# 11_LMS1_Power.net
KiCad netlist of a schematic drawn in Altium Designer
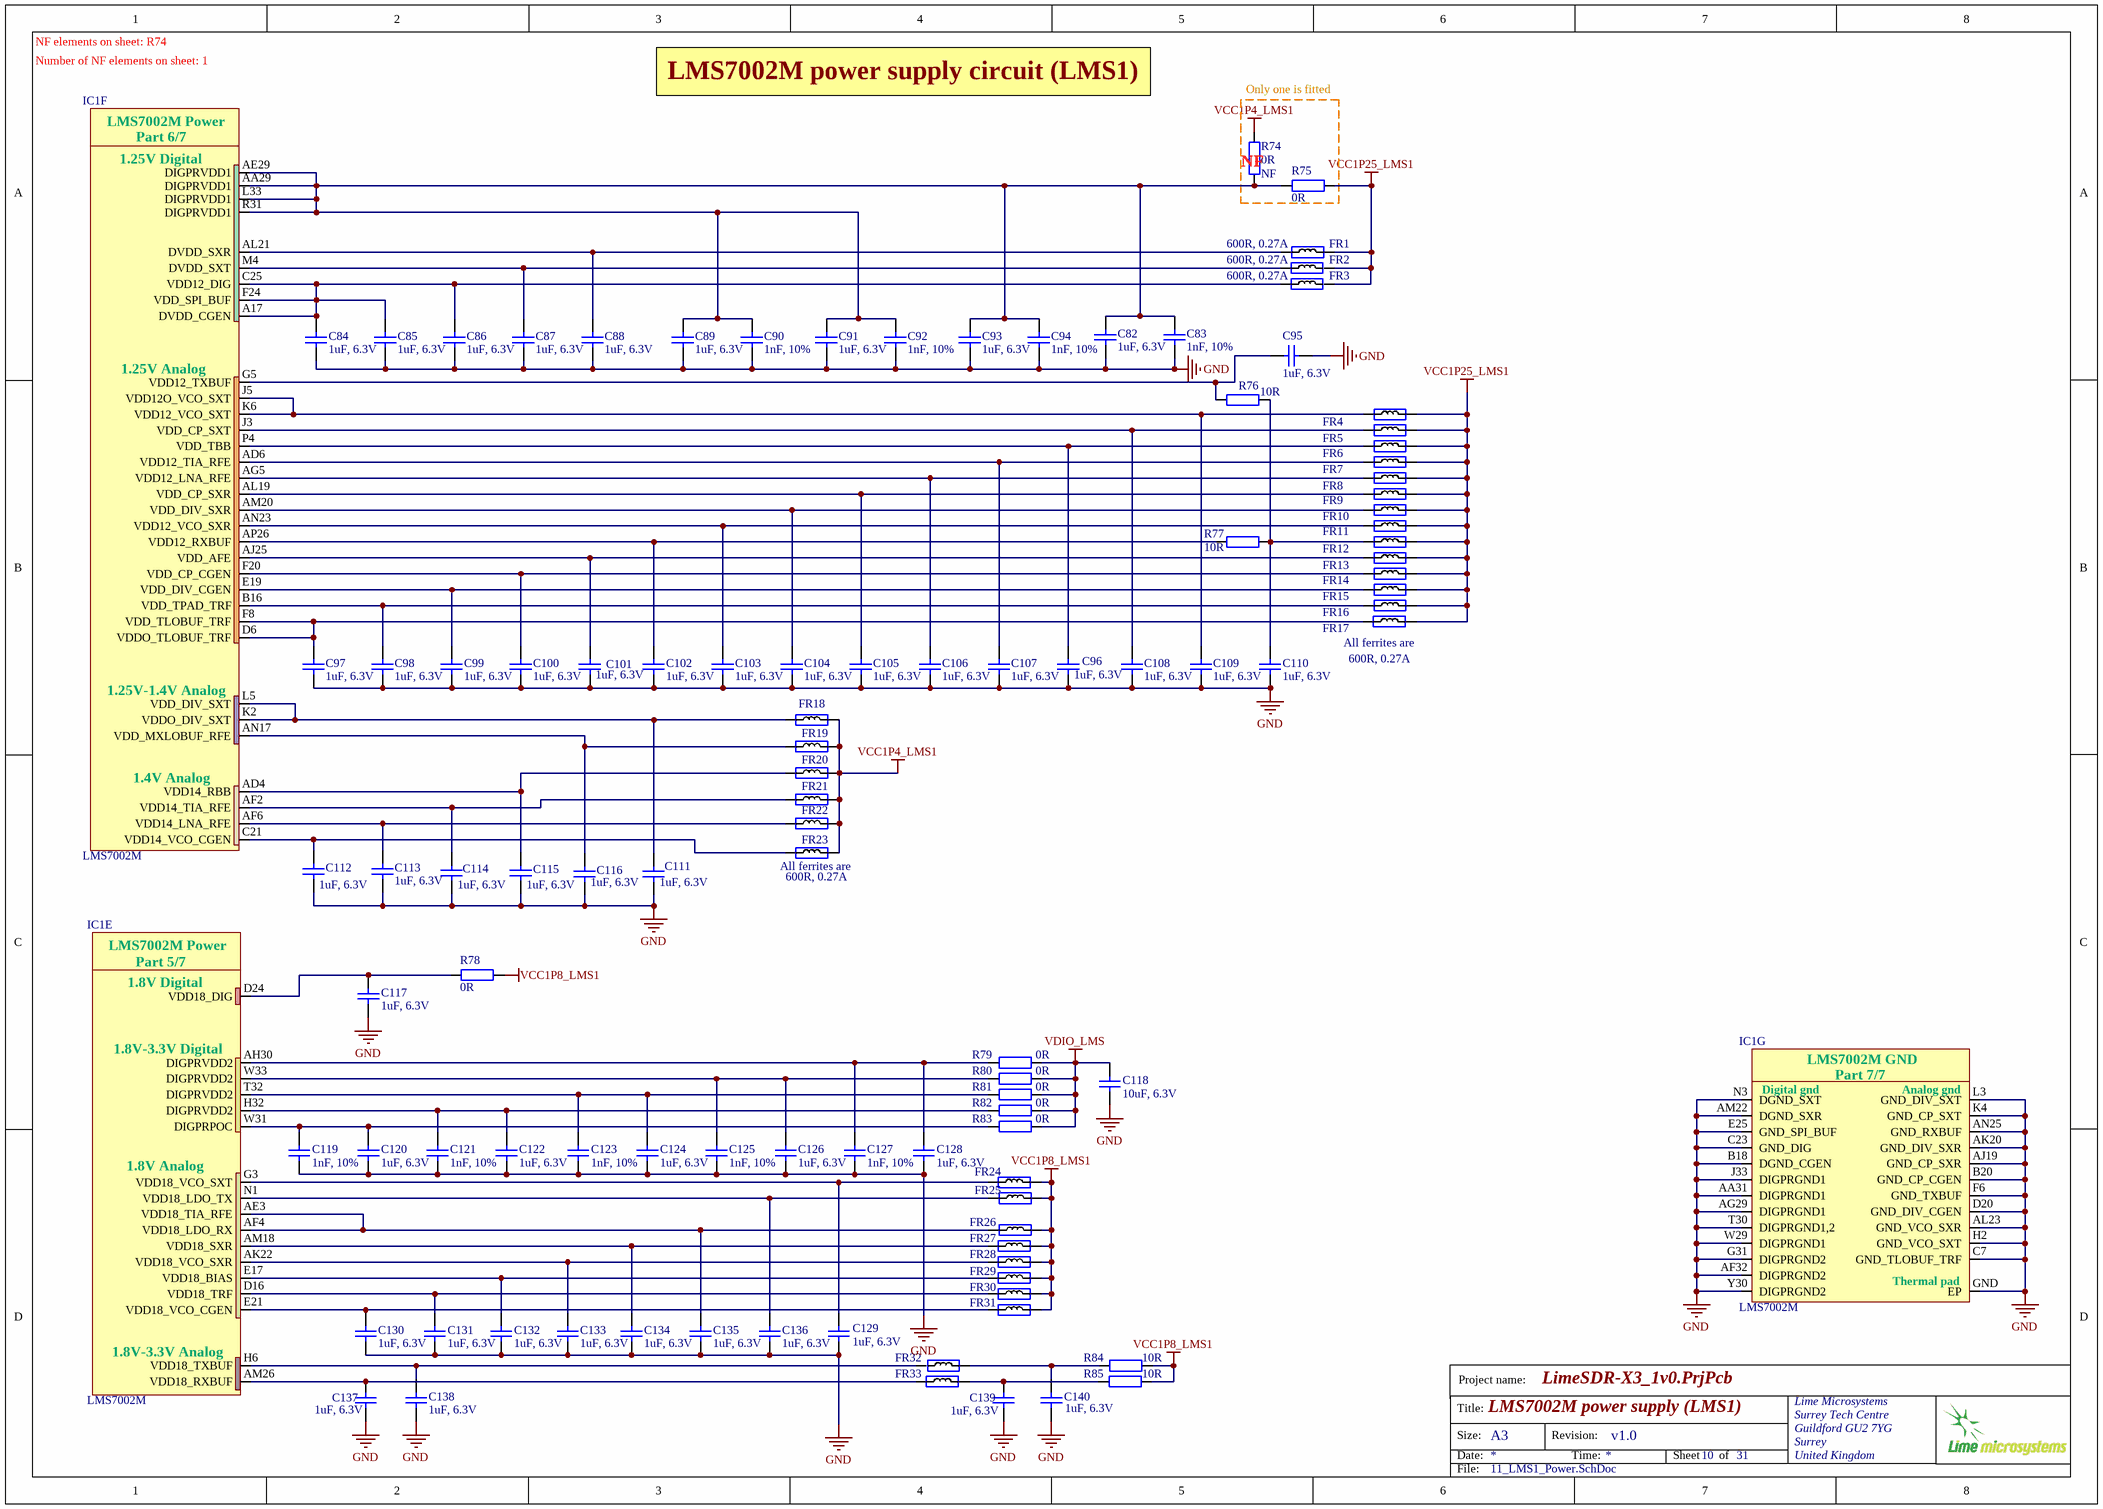
[diagram p0: 11_LMS1_Power.SchDoc]

(export (version "E")
  (design (tool "Eeschema 10.0.6"))
  (components
    (comp (ref "C82")
      (value "1uF, 6.3V")
      (footprint "CAP0201")
      (fields (field (name "TOLERANCE") "±20%") (field (name "MANUFACTURER") "TDK Corporation"))
      (libsource (lib "") (part "Cap_0402_4"))
    )
    (comp (ref "C83")
      (value "1nF, 10%")
      (footprint "CAP0201")
      (fields (field (name "TOLERANCE") "±10%") (field (name "MANUFACTURER") "TDK Corporation"))
      (libsource (lib "") (part "Cap_0402_4"))
    )
    (comp (ref "C84")
      (value "1uF, 6.3V")
      (footprint "CAP0201")
      (fields (field (name "TOLERANCE") "±20%") (field (name "MANUFACTURER") "TDK Corporation"))
      (libsource (lib "") (part "Cap_0402_2"))
    )
    (comp (ref "C85")
      (value "1uF, 6.3V")
      (footprint "CAP0201")
      (fields (field (name "TOLERANCE") "±20%") (field (name "MANUFACTURER") "TDK Corporation"))
      (libsource (lib "") (part "Cap_0402_2"))
    )
    (comp (ref "C86")
      (value "1uF, 6.3V")
      (footprint "CAP0201")
      (fields (field (name "TOLERANCE") "±20%") (field (name "MANUFACTURER") "TDK Corporation"))
      (libsource (lib "") (part "Cap_0402_2"))
    )
    (comp (ref "C87")
      (value "1uF, 6.3V")
      (footprint "CAP0201")
      (fields (field (name "TOLERANCE") "±20%") (field (name "MANUFACTURER") "TDK Corporation"))
      (libsource (lib "") (part "Cap_0402_4"))
    )
    (comp (ref "C88")
      (value "1uF, 6.3V")
      (footprint "CAP0201")
      (fields (field (name "TOLERANCE") "±20%") (field (name "MANUFACTURER") "TDK Corporation"))
      (libsource (lib "") (part "Cap_0402_2"))
    )
    (comp (ref "C89")
      (value "1uF, 6.3V")
      (footprint "CAP0201")
      (fields (field (name "TOLERANCE") "±20%") (field (name "MANUFACTURER") "TDK Corporation"))
      (libsource (lib "") (part "Cap_0402_4"))
    )
    (comp (ref "C90")
      (value "1nF, 10%")
      (footprint "CAP0201")
      (fields (field (name "TOLERANCE") "±10%") (field (name "MANUFACTURER") "TDK Corporation"))
      (libsource (lib "") (part "Cap_0402_4"))
    )
    (comp (ref "C91")
      (value "1uF, 6.3V")
      (footprint "CAP0201")
      (fields (field (name "TOLERANCE") "±20%") (field (name "MANUFACTURER") "TDK Corporation"))
      (libsource (lib "") (part "Cap_0402_4"))
    )
    (comp (ref "C92")
      (value "1nF, 10%")
      (footprint "CAP0201")
      (fields (field (name "TOLERANCE") "±10%") (field (name "MANUFACTURER") "TDK Corporation"))
      (libsource (lib "") (part "Cap_0402_4"))
    )
    (comp (ref "C93")
      (value "1uF, 6.3V")
      (footprint "CAP0201")
      (fields (field (name "TOLERANCE") "±20%") (field (name "MANUFACTURER") "TDK Corporation"))
      (libsource (lib "") (part "Cap_0402_4"))
    )
    (comp (ref "C94")
      (value "1nF, 10%")
      (footprint "CAP0201")
      (fields (field (name "TOLERANCE") "±10%") (field (name "MANUFACTURER") "TDK Corporation"))
      (libsource (lib "") (part "Cap_0402_4"))
    )
    (comp (ref "C95")
      (value "1uF, 6.3V")
      (footprint "CAP0201")
      (fields (field (name "TOLERANCE") "±20%") (field (name "MANUFACTURER") "TDK Corporation"))
      (libsource (lib "") (part "Cap_0402_1"))
    )
    (comp (ref "C96")
      (value "1uF, 6.3V")
      (footprint "CAP0201")
      (fields (field (name "TOLERANCE") "±20%") (field (name "MANUFACTURER") "TDK Corporation"))
      (libsource (lib "") (part "Cap_0402_2"))
    )
    (comp (ref "C97")
      (value "1uF, 6.3V")
      (footprint "CAP0201")
      (fields (field (name "TOLERANCE") "±20%") (field (name "MANUFACTURER") "TDK Corporation"))
      (libsource (lib "") (part "Cap_0402_2"))
    )
    (comp (ref "C98")
      (value "1uF, 6.3V")
      (footprint "CAP0201")
      (fields (field (name "TOLERANCE") "±20%") (field (name "MANUFACTURER") "TDK Corporation"))
      (libsource (lib "") (part "Cap_0402_2"))
    )
    (comp (ref "C99")
      (value "1uF, 6.3V")
      (footprint "CAP0201")
      (fields (field (name "TOLERANCE") "±20%") (field (name "MANUFACTURER") "TDK Corporation"))
      (libsource (lib "") (part "Cap_0402_2"))
    )
    (comp (ref "C100")
      (value "1uF, 6.3V")
      (footprint "CAP0201")
      (fields (field (name "TOLERANCE") "±20%") (field (name "MANUFACTURER") "TDK Corporation"))
      (libsource (lib "") (part "Cap_0402_4"))
    )
    (comp (ref "C101")
      (value "1uF, 6.3V")
      (footprint "CAP0201")
      (fields (field (name "TOLERANCE") "±20%") (field (name "MANUFACTURER") "TDK Corporation"))
      (libsource (lib "") (part "Cap_0402_2"))
    )
    (comp (ref "C102")
      (value "1uF, 6.3V")
      (footprint "CAP0201")
      (fields (field (name "TOLERANCE") "±20%") (field (name "MANUFACTURER") "TDK Corporation"))
      (libsource (lib "") (part "Cap_0402_2"))
    )
    (comp (ref "C103")
      (value "1uF, 6.3V")
      (footprint "CAP0201")
      (fields (field (name "TOLERANCE") "±20%") (field (name "MANUFACTURER") "TDK Corporation"))
      (libsource (lib "") (part "Cap_0402_2"))
    )
    (comp (ref "C104")
      (value "1uF, 6.3V")
      (footprint "CAP0201")
      (fields (field (name "TOLERANCE") "±20%") (field (name "MANUFACTURER") "TDK Corporation"))
      (libsource (lib "") (part "Cap_0402_2"))
    )
    (comp (ref "C105")
      (value "1uF, 6.3V")
      (footprint "CAP0201")
      (fields (field (name "TOLERANCE") "±20%") (field (name "MANUFACTURER") "TDK Corporation"))
      (libsource (lib "") (part "Cap_0402_2"))
    )
    (comp (ref "C106")
      (value "1uF, 6.3V")
      (footprint "CAP0201")
      (fields (field (name "TOLERANCE") "±20%") (field (name "MANUFACTURER") "TDK Corporation"))
      (libsource (lib "") (part "Cap_0402_2"))
    )
    (comp (ref "C107")
      (value "1uF, 6.3V")
      (footprint "CAP0201")
      (fields (field (name "TOLERANCE") "±20%") (field (name "MANUFACTURER") "TDK Corporation"))
      (libsource (lib "") (part "Cap_0402_4"))
    )
    (comp (ref "C108")
      (value "1uF, 6.3V")
      (footprint "CAP0201")
      (fields (field (name "TOLERANCE") "±20%") (field (name "MANUFACTURER") "TDK Corporation"))
      (libsource (lib "") (part "Cap_0402_2"))
    )
    (comp (ref "C109")
      (value "1uF, 6.3V")
      (footprint "CAP0201")
      (fields (field (name "TOLERANCE") "±20%") (field (name "MANUFACTURER") "TDK Corporation"))
      (libsource (lib "") (part "Cap_0402_4"))
    )
    (comp (ref "C110")
      (value "1uF, 6.3V")
      (footprint "CAP0201")
      (fields (field (name "TOLERANCE") "±20%") (field (name "MANUFACTURER") "TDK Corporation"))
      (libsource (lib "") (part "Cap_0402_4"))
    )
    (comp (ref "C111")
      (value "1uF, 6.3V")
      (footprint "CAP0201")
      (fields (field (name "TOLERANCE") "±20%") (field (name "MANUFACTURER") "TDK Corporation"))
      (libsource (lib "") (part "Cap_0402_2"))
    )
    (comp (ref "C112")
      (value "1uF, 6.3V")
      (footprint "CAP0201")
      (fields (field (name "TOLERANCE") "±20%") (field (name "MANUFACTURER") "TDK Corporation"))
      (libsource (lib "") (part "Cap_0402_2"))
    )
    (comp (ref "C113")
      (value "1uF, 6.3V")
      (footprint "CAP0201")
      (fields (field (name "TOLERANCE") "±20%") (field (name "MANUFACTURER") "TDK Corporation"))
      (libsource (lib "") (part "Cap_0402_2"))
    )
    (comp (ref "C114")
      (value "1uF, 6.3V")
      (footprint "CAP0201")
      (fields (field (name "TOLERANCE") "±20%") (field (name "MANUFACTURER") "TDK Corporation"))
      (libsource (lib "") (part "Cap_0402_3"))
    )
    (comp (ref "C115")
      (value "1uF, 6.3V")
      (footprint "CAP0201")
      (fields (field (name "TOLERANCE") "±20%") (field (name "MANUFACTURER") "TDK Corporation"))
      (libsource (lib "") (part "Cap_0402_3"))
    )
    (comp (ref "C116")
      (value "1uF, 6.3V")
      (footprint "CAP0201")
      (fields (field (name "TOLERANCE") "±20%") (field (name "MANUFACTURER") "TDK Corporation"))
      (libsource (lib "") (part "Cap_0402_2"))
    )
    (comp (ref "C117")
      (value "1uF, 6.3V")
      (footprint "CAP0201")
      (fields (field (name "TOLERANCE") "±20%") (field (name "MANUFACTURER") "TDK Corporation"))
      (libsource (lib "LimeMicroAltiumLib_schLib") (part "Cap_0402"))
    )
    (comp (ref "C118")
      (value "10uF, 6.3V")
      (footprint "CAP0603")
      (fields (field (name "TOLERANCE") "±20%") (field (name "MANUFACTURER") "Yageo"))
      (libsource (lib "LimeFPGAboard_schLib") (part "Cap_0603"))
    )
    (comp (ref "C119")
      (value "1nF, 10%")
      (footprint "CAP0201")
      (fields (field (name "TOLERANCE") "±10%") (field (name "MANUFACTURER") "TDK Corporation"))
      (libsource (lib "LimeMicroAltiumLib_schLib") (part "Cap_0402"))
    )
    (comp (ref "C120")
      (value "1uF, 6.3V")
      (footprint "CAP0201")
      (fields (field (name "TOLERANCE") "±20%") (field (name "MANUFACTURER") "TDK Corporation"))
      (libsource (lib "LimeMicroAltiumLib_schLib") (part "Cap_0402"))
    )
    (comp (ref "C121")
      (value "1nF, 10%")
      (footprint "CAP0201")
      (fields (field (name "TOLERANCE") "±10%") (field (name "MANUFACTURER") "TDK Corporation"))
      (libsource (lib "LimeMicroAltiumLib_schLib") (part "Cap_0402"))
    )
    (comp (ref "C122")
      (value "1uF, 6.3V")
      (footprint "CAP0201")
      (fields (field (name "TOLERANCE") "±20%") (field (name "MANUFACTURER") "TDK Corporation"))
      (libsource (lib "LimeMicroAltiumLib_schLib") (part "Cap_0402"))
    )
    (comp (ref "C123")
      (value "1nF, 10%")
      (footprint "CAP0201")
      (fields (field (name "TOLERANCE") "±10%") (field (name "MANUFACTURER") "TDK Corporation"))
      (libsource (lib "LimeMicroAltiumLib_schLib") (part "Cap_0402"))
    )
    (comp (ref "C124")
      (value "1uF, 6.3V")
      (footprint "CAP0201")
      (fields (field (name "TOLERANCE") "±20%") (field (name "MANUFACTURER") "TDK Corporation"))
      (libsource (lib "LimeMicroAltiumLib_schLib") (part "Cap_0402"))
    )
    (comp (ref "C125")
      (value "1nF, 10%")
      (footprint "CAP0201")
      (fields (field (name "TOLERANCE") "±10%") (field (name "MANUFACTURER") "TDK Corporation"))
      (libsource (lib "LimeMicroAltiumLib_schLib") (part "Cap_0402"))
    )
    (comp (ref "C126")
      (value "1uF, 6.3V")
      (footprint "CAP0201")
      (fields (field (name "TOLERANCE") "±20%") (field (name "MANUFACTURER") "TDK Corporation"))
      (libsource (lib "LimeMicroAltiumLib_schLib") (part "Cap_0402"))
    )
    (comp (ref "C127")
      (value "1nF, 10%")
      (footprint "CAP0201")
      (fields (field (name "TOLERANCE") "±10%") (field (name "MANUFACTURER") "TDK Corporation"))
      (libsource (lib "LimeMicroAltiumLib_schLib") (part "Cap_0402"))
    )
    (comp (ref "C128")
      (value "1uF, 6.3V")
      (footprint "CAP0201")
      (fields (field (name "TOLERANCE") "±20%") (field (name "MANUFACTURER") "TDK Corporation"))
      (libsource (lib "LimeMicroAltiumLib_schLib") (part "Cap_0402"))
    )
    (comp (ref "C129")
      (value "1uF, 6.3V")
      (footprint "CAP0201")
      (fields (field (name "TOLERANCE") "±20%") (field (name "MANUFACTURER") "TDK Corporation"))
      (libsource (lib "LimeMicroAltiumLib_schLib") (part "Cap_0402"))
    )
    (comp (ref "C130")
      (value "1uF, 6.3V")
      (footprint "CAP0201")
      (fields (field (name "TOLERANCE") "±20%") (field (name "MANUFACTURER") "TDK Corporation"))
      (libsource (lib "LimeMicroAltiumLib_schLib") (part "Cap_0402"))
    )
    (comp (ref "C131")
      (value "1uF, 6.3V")
      (footprint "CAP0201")
      (fields (field (name "TOLERANCE") "±20%") (field (name "MANUFACTURER") "TDK Corporation"))
      (libsource (lib "LimeMicroAltiumLib_schLib") (part "Cap_0402"))
    )
    (comp (ref "C132")
      (value "1uF, 6.3V")
      (footprint "CAP0201")
      (fields (field (name "TOLERANCE") "±20%") (field (name "MANUFACTURER") "TDK Corporation"))
      (libsource (lib "LimeMicroAltiumLib_schLib") (part "Cap_0402"))
    )
    (comp (ref "C133")
      (value "1uF, 6.3V")
      (footprint "CAP0201")
      (fields (field (name "TOLERANCE") "±20%") (field (name "MANUFACTURER") "TDK Corporation"))
      (libsource (lib "LimeMicroAltiumLib_schLib") (part "Cap_0402"))
    )
    (comp (ref "C134")
      (value "1uF, 6.3V")
      (footprint "CAP0201")
      (fields (field (name "TOLERANCE") "±20%") (field (name "MANUFACTURER") "TDK Corporation"))
      (libsource (lib "LimeMicroAltiumLib_schLib") (part "Cap_0402"))
    )
    (comp (ref "C135")
      (value "1uF, 6.3V")
      (footprint "CAP0201")
      (fields (field (name "TOLERANCE") "±20%") (field (name "MANUFACTURER") "TDK Corporation"))
      (libsource (lib "LimeMicroAltiumLib_schLib") (part "Cap_0402"))
    )
    (comp (ref "C136")
      (value "1uF, 6.3V")
      (footprint "CAP0201")
      (fields (field (name "TOLERANCE") "±20%") (field (name "MANUFACTURER") "TDK Corporation"))
      (libsource (lib "LimeMicroAltiumLib_schLib") (part "Cap_0402"))
    )
    (comp (ref "C137")
      (value "1uF, 6.3V")
      (footprint "CAP0201")
      (fields (field (name "TOLERANCE") "±20%") (field (name "MANUFACTURER") "TDK Corporation"))
      (libsource (lib "LimeMicroAltiumLib_schLib") (part "Cap_0402"))
    )
    (comp (ref "C138")
      (value "1uF, 6.3V")
      (footprint "CAP0201")
      (fields (field (name "TOLERANCE") "±20%") (field (name "MANUFACTURER") "TDK Corporation"))
      (libsource (lib "LimeMicroAltiumLib_schLib") (part "Cap_0402"))
    )
    (comp (ref "C139")
      (value "1uF, 6.3V")
      (footprint "CAP0201")
      (fields (field (name "TOLERANCE") "±20%") (field (name "MANUFACTURER") "TDK Corporation"))
      (libsource (lib "LimeMicroAltiumLib_schLib") (part "Cap_0402"))
    )
    (comp (ref "C140")
      (value "1uF, 6.3V")
      (footprint "CAP0201")
      (fields (field (name "TOLERANCE") "±20%") (field (name "MANUFACTURER") "TDK Corporation"))
      (libsource (lib "LimeMicroAltiumLib_schLib") (part "Cap_0402"))
    )
    (comp (ref "FR1")
      (value "600R, 0.27A")
      (footprint "RES0201")
      (fields (field (name "MANUFACTURER") "Taiyo Yuden"))
      (libsource (lib "LimeMicroAltiumLib_schLib") (part "Ferrite"))
    )
    (comp (ref "FR2")
      (value "600R, 0.27A")
      (footprint "RES0201")
      (fields (field (name "MANUFACTURER") "Taiyo Yuden"))
      (libsource (lib "") (part "Ferrite_2"))
    )
    (comp (ref "FR3")
      (value "600R, 0.27A")
      (footprint "RES0201")
      (fields (field (name "MANUFACTURER") "Taiyo Yuden"))
      (libsource (lib "") (part "Ferrite_2"))
    )
    (comp (ref "FR4")
      (value "600R, 0.27A")
      (footprint "RES0201")
      (fields (field (name "MANUFACTURER") "Taiyo Yuden"))
      (libsource (lib "LimeMicroAltiumLib_schLib") (part "Ferrite"))
    )
    (comp (ref "FR5")
      (value "600R, 0.27A")
      (footprint "RES0201")
      (fields (field (name "MANUFACTURER") "Taiyo Yuden"))
      (libsource (lib "LimeMicroAltiumLib_schLib") (part "Ferrite"))
    )
    (comp (ref "FR6")
      (value "600R, 0.27A")
      (footprint "RES0201")
      (fields (field (name "MANUFACTURER") "Taiyo Yuden"))
      (libsource (lib "LimeMicroAltiumLib_schLib") (part "Ferrite"))
    )
    (comp (ref "FR7")
      (value "600R, 0.27A")
      (footprint "RES0201")
      (fields (field (name "MANUFACTURER") "Taiyo Yuden"))
      (libsource (lib "LimeMicroAltiumLib_schLib") (part "Ferrite"))
    )
    (comp (ref "FR8")
      (value "600R, 0.27A")
      (footprint "RES0201")
      (fields (field (name "MANUFACTURER") "Taiyo Yuden"))
      (libsource (lib "LimeMicroAltiumLib_schLib") (part "Ferrite"))
    )
    (comp (ref "FR9")
      (value "600R, 0.27A")
      (footprint "RES0201")
      (fields (field (name "MANUFACTURER") "Taiyo Yuden"))
      (libsource (lib "LimeMicroAltiumLib_schLib") (part "Ferrite"))
    )
    (comp (ref "FR10")
      (value "600R, 0.27A")
      (footprint "RES0201")
      (fields (field (name "MANUFACTURER") "Taiyo Yuden"))
      (libsource (lib "LimeMicroAltiumLib_schLib") (part "Ferrite"))
    )
    (comp (ref "FR11")
      (value "600R, 0.27A")
      (footprint "RES0201")
      (fields (field (name "MANUFACTURER") "Taiyo Yuden"))
      (libsource (lib "LimeMicroAltiumLib_schLib") (part "Ferrite"))
    )
    (comp (ref "FR12")
      (value "600R, 0.27A")
      (footprint "RES0201")
      (fields (field (name "MANUFACTURER") "Taiyo Yuden"))
      (libsource (lib "LimeMicroAltiumLib_schLib") (part "Ferrite"))
    )
    (comp (ref "FR13")
      (value "600R, 0.27A")
      (footprint "RES0201")
      (fields (field (name "MANUFACTURER") "Taiyo Yuden"))
      (libsource (lib "LimeMicroAltiumLib_schLib") (part "Ferrite"))
    )
    (comp (ref "FR14")
      (value "600R, 0.27A")
      (footprint "RES0201")
      (fields (field (name "MANUFACTURER") "Taiyo Yuden"))
      (libsource (lib "LimeMicroAltiumLib_schLib") (part "Ferrite"))
    )
    (comp (ref "FR15")
      (value "600R, 0.27A")
      (footprint "RES0201")
      (fields (field (name "MANUFACTURER") "Taiyo Yuden"))
      (libsource (lib "LimeMicroAltiumLib_schLib") (part "Ferrite"))
    )
    (comp (ref "FR16")
      (value "600R, 0.27A")
      (footprint "RES0201")
      (fields (field (name "MANUFACTURER") "Taiyo Yuden"))
      (libsource (lib "LimeMicroAltiumLib_schLib") (part "Ferrite"))
    )
    (comp (ref "FR17")
      (value "600R, 0.27A")
      (footprint "RES0201")
      (fields (field (name "MANUFACTURER") "Taiyo Yuden"))
      (libsource (lib "") (part "Ferrite_2"))
    )
    (comp (ref "FR18")
      (value "600R, 0.27A")
      (footprint "RES0201")
      (fields (field (name "MANUFACTURER") "Taiyo Yuden"))
      (libsource (lib "") (part "Ferrite_2"))
    )
    (comp (ref "FR19")
      (value "600R, 0.27A")
      (footprint "RES0201")
      (fields (field (name "MANUFACTURER") "Taiyo Yuden"))
      (libsource (lib "") (part "Ferrite_2"))
    )
    (comp (ref "FR20")
      (value "600R, 0.27A")
      (footprint "RES0201")
      (fields (field (name "MANUFACTURER") "Taiyo Yuden"))
      (libsource (lib "") (part "Ferrite_2"))
    )
    (comp (ref "FR21")
      (value "600R, 0.27A")
      (footprint "RES0201")
      (fields (field (name "MANUFACTURER") "Taiyo Yuden"))
      (libsource (lib "") (part "Ferrite_2"))
    )
    (comp (ref "FR22")
      (value "600R, 0.27A")
      (footprint "RES0201")
      (fields (field (name "MANUFACTURER") "Taiyo Yuden"))
      (libsource (lib "") (part "Ferrite_2"))
    )
    (comp (ref "FR23")
      (value "600R, 0.27A")
      (footprint "RES0201")
      (fields (field (name "MANUFACTURER") "Taiyo Yuden"))
      (libsource (lib "") (part "Ferrite_2"))
    )
    (comp (ref "FR24")
      (value "600R, 0.27A")
      (footprint "RES0201")
      (fields (field (name "MANUFACTURER") "Taiyo Yuden"))
      (libsource (lib "") (part "Ferrite_2"))
    )
    (comp (ref "FR25")
      (value "600R, 0.27A")
      (footprint "RES0201")
      (fields (field (name "MANUFACTURER") "Taiyo Yuden"))
      (libsource (lib "") (part "Ferrite_1"))
    )
    (comp (ref "FR26")
      (value "600R, 0.27A")
      (footprint "RES0201")
      (fields (field (name "MANUFACTURER") "Taiyo Yuden"))
      (libsource (lib "") (part "Ferrite_1"))
    )
    (comp (ref "FR27")
      (value "600R, 0.27A")
      (footprint "RES0201")
      (fields (field (name "MANUFACTURER") "Taiyo Yuden"))
      (libsource (lib "") (part "Ferrite_2"))
    )
    (comp (ref "FR28")
      (value "600R, 0.27A")
      (footprint "RES0201")
      (fields (field (name "MANUFACTURER") "Taiyo Yuden"))
      (libsource (lib "") (part "Ferrite_2"))
    )
    (comp (ref "FR29")
      (value "600R, 0.27A")
      (footprint "RES0201")
      (fields (field (name "MANUFACTURER") "Taiyo Yuden"))
      (libsource (lib "") (part "Ferrite_2"))
    )
    (comp (ref "FR30")
      (value "600R, 0.27A")
      (footprint "RES0201")
      (fields (field (name "MANUFACTURER") "Taiyo Yuden"))
      (libsource (lib "") (part "Ferrite_2"))
    )
    (comp (ref "FR31")
      (value "600R, 0.27A")
      (footprint "RES0201")
      (fields (field (name "MANUFACTURER") "Taiyo Yuden"))
      (libsource (lib "") (part "Ferrite_2"))
    )
    (comp (ref "FR32")
      (value "600R, 0.27A")
      (footprint "RES0201")
      (fields (field (name "MANUFACTURER") "Taiyo Yuden"))
      (libsource (lib "") (part "Ferrite_1"))
    )
    (comp (ref "FR33")
      (value "600R, 0.27A")
      (footprint "RES0201")
      (fields (field (name "MANUFACTURER") "Taiyo Yuden"))
      (libsource (lib "") (part "Ferrite_2"))
    )
    (comp (ref "IC1")
      (value "LMS7002M")
      (footprint "LMS7002M_v5")
      (description "Schematic symbol revision 4. Default footprint - 0.31mm pad")
      (fields (field (name "MANUFACTURER") "Lime Microsystems"))
      (libsource (lib "LimeMicroAltiumLib_schLib_r04") (part "LMS7002Mr4"))
    )
    (comp (ref "R74")
      (value "0R")
      (footprint "RES0402")
      (fields
        (field (name "ASSEMBLY INFO") "NF")
        (field (name "MANUFACTURER") "Yageo")
        (field (name "TOLERANCE") "Jumper")
      )
      (libsource (lib "LimeMicroAltiumLib_schLib") (part "Res_0402"))
    )
    (comp (ref "R75")
      (value "0R")
      (footprint "RES0402")
      (fields (field (name "MANUFACTURER") "Yageo") (field (name "TOLERANCE") "Jumper"))
      (libsource (lib "") (part "Res_0402_1"))
    )
    (comp (ref "R76")
      (value "10R")
      (footprint "RES0201")
      (fields
        (field (name "MANUFACTURER") "Panasonic Electronic Components")
        (field (name "TOLERANCE") "±1%")
      )
      (libsource (lib "LimeMicroAltiumLib_schLib") (part "Res_0402"))
    )
    (comp (ref "R77")
      (value "10R")
      (footprint "RES0201")
      (fields
        (field (name "MANUFACTURER") "Panasonic Electronic Components")
        (field (name "TOLERANCE") "±1%")
      )
      (libsource (lib "LimeMicroAltiumLib_schLib") (part "Res_0402"))
    )
    (comp (ref "R78")
      (value "0R")
      (footprint "RES0201")
      (fields (field (name "MANUFACTURER") "Rohm Semiconductor") (field (name "TOLERANCE") "Jumper"))
      (libsource (lib "LimeMicroAltiumLib_schLib") (part "Res_0402"))
    )
    (comp (ref "R79")
      (value "0R")
      (footprint "RES0402")
      (fields (field (name "MANUFACTURER") "Yageo") (field (name "TOLERANCE") "Jumper"))
      (libsource (lib "LimeMicroAltiumLib_schLib") (part "Res_0402"))
    )
    (comp (ref "R80")
      (value "0R")
      (footprint "RES0402")
      (fields (field (name "MANUFACTURER") "Yageo") (field (name "TOLERANCE") "Jumper"))
      (libsource (lib "LimeMicroAltiumLib_schLib") (part "Res_0402"))
    )
    (comp (ref "R81")
      (value "0R")
      (footprint "RES0402")
      (fields (field (name "MANUFACTURER") "Yageo") (field (name "TOLERANCE") "Jumper"))
      (libsource (lib "LimeMicroAltiumLib_schLib") (part "Res_0402"))
    )
    (comp (ref "R82")
      (value "0R")
      (footprint "RES0402")
      (fields (field (name "MANUFACTURER") "Yageo") (field (name "TOLERANCE") "Jumper"))
      (libsource (lib "LimeMicroAltiumLib_schLib") (part "Res_0402"))
    )
    (comp (ref "R83")
      (value "0R")
      (footprint "RES0402")
      (fields (field (name "MANUFACTURER") "Yageo") (field (name "TOLERANCE") "Jumper"))
      (libsource (lib "LimeMicroAltiumLib_schLib") (part "Res_0402"))
    )
    (comp (ref "R84")
      (value "10R")
      (footprint "RES0201")
      (fields
        (field (name "MANUFACTURER") "Panasonic Electronic Components")
        (field (name "TOLERANCE") "±1%")
      )
      (libsource (lib "LimeMicroAltiumLib_schLib") (part "Res_0402"))
    )
    (comp (ref "R85")
      (value "10R")
      (footprint "RES0201")
      (fields
        (field (name "MANUFACTURER") "Panasonic Electronic Components")
        (field (name "TOLERANCE") "±1%")
      )
      (libsource (lib "LimeMicroAltiumLib_schLib") (part "Res_0402"))
    )
  )
  (nets
    (net (code "1") (name "GND") (class "Default")
      (node (ref "C100") (pin "1") (pinfunction "1_1") (pintype "passive"))
      (node (ref "C101") (pin "2") (pinfunction "2_2") (pintype "passive"))
      (node (ref "C102") (pin "2") (pinfunction "2_2") (pintype "passive"))
      (node (ref "C103") (pin "2") (pinfunction "2_2") (pintype "passive"))
      (node (ref "C104") (pin "2") (pinfunction "2_2") (pintype "passive"))
      (node (ref "C105") (pin "2") (pinfunction "2_2") (pintype "passive"))
      (node (ref "C106") (pin "2") (pinfunction "2_2") (pintype "passive"))
      (node (ref "C107") (pin "1") (pinfunction "1_1") (pintype "passive"))
      (node (ref "C108") (pin "2") (pinfunction "2_2") (pintype "passive"))
      (node (ref "C109") (pin "1") (pinfunction "1_1") (pintype "passive"))
      (node (ref "C110") (pin "1") (pinfunction "1_1") (pintype "passive"))
      (node (ref "C111") (pin "2") (pinfunction "2_2") (pintype "passive"))
      (node (ref "C112") (pin "2") (pinfunction "2_2") (pintype "passive"))
      (node (ref "C113") (pin "2") (pinfunction "2_2") (pintype "passive"))
      (node (ref "C114") (pin "2") (pinfunction "2_2") (pintype "passive"))
      (node (ref "C115") (pin "2") (pinfunction "2_2") (pintype "passive"))
      (node (ref "C116") (pin "2") (pinfunction "2_2") (pintype "passive"))
      (node (ref "C117") (pin "2") (pinfunction "2_2") (pintype "passive"))
      (node (ref "C118") (pin "1") (pinfunction "1_1") (pintype "passive"))
      (node (ref "C119") (pin "2") (pinfunction "2_2") (pintype "passive"))
      (node (ref "C120") (pin "2") (pinfunction "2_2") (pintype "passive"))
      (node (ref "C121") (pin "2") (pinfunction "2_2") (pintype "passive"))
      (node (ref "C122") (pin "2") (pinfunction "2_2") (pintype "passive"))
      (node (ref "C123") (pin "2") (pinfunction "2_2") (pintype "passive"))
      (node (ref "C124") (pin "2") (pinfunction "2_2") (pintype "passive"))
      (node (ref "C125") (pin "2") (pinfunction "2_2") (pintype "passive"))
      (node (ref "C126") (pin "2") (pinfunction "2_2") (pintype "passive"))
      (node (ref "C127") (pin "2") (pinfunction "2_2") (pintype "passive"))
      (node (ref "C128") (pin "2") (pinfunction "2_2") (pintype "passive"))
      (node (ref "C129") (pin "2") (pinfunction "2_2") (pintype "passive"))
      (node (ref "C130") (pin "2") (pinfunction "2_2") (pintype "passive"))
      (node (ref "C131") (pin "2") (pinfunction "2_2") (pintype "passive"))
      (node (ref "C132") (pin "2") (pinfunction "2_2") (pintype "passive"))
      (node (ref "C133") (pin "2") (pinfunction "2_2") (pintype "passive"))
      (node (ref "C134") (pin "2") (pinfunction "2_2") (pintype "passive"))
      (node (ref "C135") (pin "2") (pinfunction "2_2") (pintype "passive"))
      (node (ref "C136") (pin "2") (pinfunction "2_2") (pintype "passive"))
      (node (ref "C137") (pin "2") (pinfunction "2_2") (pintype "passive"))
      (node (ref "C138") (pin "2") (pinfunction "2_2") (pintype "passive"))
      (node (ref "C139") (pin "2") (pinfunction "2_2") (pintype "passive"))
      (node (ref "C140") (pin "2") (pinfunction "2_2") (pintype "passive"))
      (node (ref "C82") (pin "2") (pinfunction "2_2") (pintype "passive"))
      (node (ref "C83") (pin "2") (pinfunction "2_2") (pintype "passive"))
      (node (ref "C84") (pin "2") (pinfunction "2_2") (pintype "passive"))
      (node (ref "C85") (pin "2") (pinfunction "2_2") (pintype "passive"))
      (node (ref "C86") (pin "2") (pinfunction "2_2") (pintype "passive"))
      (node (ref "C87") (pin "1") (pinfunction "1_1") (pintype "passive"))
      (node (ref "C88") (pin "2") (pinfunction "2_2") (pintype "passive"))
      (node (ref "C89") (pin "2") (pinfunction "2_2") (pintype "passive"))
      (node (ref "C90") (pin "2") (pinfunction "2_2") (pintype "passive"))
      (node (ref "C91") (pin "2") (pinfunction "2_2") (pintype "passive"))
      (node (ref "C92") (pin "2") (pinfunction "2_2") (pintype "passive"))
      (node (ref "C93") (pin "2") (pinfunction "2_2") (pintype "passive"))
      (node (ref "C94") (pin "2") (pinfunction "2_2") (pintype "passive"))
      (node (ref "C95") (pin "2") (pinfunction "2_2") (pintype "passive"))
      (node (ref "C96") (pin "2") (pinfunction "2_2") (pintype "passive"))
      (node (ref "C97") (pin "2") (pinfunction "2_2") (pintype "passive"))
      (node (ref "C98") (pin "2") (pinfunction "2_2") (pintype "passive"))
      (node (ref "C99") (pin "2") (pinfunction "2_2") (pintype "passive"))
      (node (ref "IC1") (pin "AA31") (pinfunction "DIGPRGND1_AA31") (pintype "passive"))
      (node (ref "IC1") (pin "AF32") (pinfunction "DIGPRGND2_AF32") (pintype "passive"))
      (node (ref "IC1") (pin "AG29") (pinfunction "DIGPRGND1_AG29") (pintype "passive"))
      (node (ref "IC1") (pin "AJ19") (pinfunction "GND_CP_SXR_AJ19") (pintype "passive"))
      (node (ref "IC1") (pin "AK20") (pinfunction "GND_DIV_SXR_AK20") (pintype "passive"))
      (node (ref "IC1") (pin "AL23") (pinfunction "GND_VCO_SXR_AL23") (pintype "passive"))
      (node (ref "IC1") (pin "AM22") (pinfunction "DGND_SXR_AM22") (pintype "passive"))
      (node (ref "IC1") (pin "AN25") (pinfunction "GND_RXBUF_AN25") (pintype "passive"))
      (node (ref "IC1") (pin "B18") (pinfunction "DGND_CGEN_B18") (pintype "passive"))
      (node (ref "IC1") (pin "B20") (pinfunction "GND_CP_CGEN_B20") (pintype "passive"))
      (node (ref "IC1") (pin "C23") (pinfunction "GND_DIG_C23") (pintype "passive"))
      (node (ref "IC1") (pin "C7") (pinfunction "GND_TLOBUF_TRF_C7") (pintype "passive"))
      (node (ref "IC1") (pin "D20") (pinfunction "GND_DIV_CGEN_D20") (pintype "passive"))
      (node (ref "IC1") (pin "E25") (pinfunction "GND_SPI_BUF_E25") (pintype "passive"))
      (node (ref "IC1") (pin "F6") (pinfunction "GND_TXBUF_F6") (pintype "passive"))
      (node (ref "IC1") (pin "G31") (pinfunction "DIGPRGND2_G31") (pintype "passive"))
      (node (ref "IC1") (pin "GND") (pinfunction "EP_GND") (pintype "passive"))
      (node (ref "IC1") (pin "H2") (pinfunction "GND_VCO_SXT_H2") (pintype "passive"))
      (node (ref "IC1") (pin "J33") (pinfunction "DIGPRGND1_J33") (pintype "passive"))
      (node (ref "IC1") (pin "K4") (pinfunction "GND_CP_SXT_K4") (pintype "passive"))
      (node (ref "IC1") (pin "L3") (pinfunction "GND_DIV_SXT_L3") (pintype "passive"))
      (node (ref "IC1") (pin "N3") (pinfunction "DGND_SXT_N3") (pintype "passive"))
      (node (ref "IC1") (pin "T30") (pinfunction "DIGPRGND1,2_T30") (pintype "passive"))
      (node (ref "IC1") (pin "W29") (pinfunction "DIGPRGND1_W29") (pintype "passive"))
      (node (ref "IC1") (pin "Y30") (pinfunction "DIGPRGND2_Y30") (pintype "passive"))
    )
    (net (code "2") (name "Net-(C82-Pad1)") (class "Default")
      (node (ref "C82") (pin "1") (pinfunction "1_1") (pintype "passive"))
      (node (ref "C83") (pin "1") (pinfunction "1_1") (pintype "passive"))
      (node (ref "C89") (pin "1") (pinfunction "1_1") (pintype "passive"))
      (node (ref "C90") (pin "1") (pinfunction "1_1") (pintype "passive"))
      (node (ref "C91") (pin "1") (pinfunction "1_1") (pintype "passive"))
      (node (ref "C92") (pin "1") (pinfunction "1_1") (pintype "passive"))
      (node (ref "C93") (pin "1") (pinfunction "1_1") (pintype "passive"))
      (node (ref "C94") (pin "1") (pinfunction "1_1") (pintype "passive"))
      (node (ref "IC1") (pin "AA29") (pinfunction "DIGPRVDD1_AA29") (pintype "power_in"))
      (node (ref "IC1") (pin "AE29") (pinfunction "DIGPRVDD1_AE29") (pintype "power_in"))
      (node (ref "IC1") (pin "L33") (pinfunction "DIGPRVDD1_L33") (pintype "power_in"))
      (node (ref "IC1") (pin "R31") (pinfunction "DIGPRVDD1_R31") (pintype "power_in"))
      (node (ref "R74") (pin "2") (pinfunction "2_2") (pintype "passive"))
      (node (ref "R75") (pin "2") (pinfunction "2_2") (pintype "passive"))
    )
    (net (code "3") (name "Net-(C110-Pad2)") (class "Default")
      (node (ref "C110") (pin "2") (pinfunction "2_2") (pintype "passive"))
      (node (ref "FR12") (pin "1") (pinfunction "1_1") (pintype "passive"))
      (node (ref "R76") (pin "2") (pinfunction "2_2") (pintype "passive"))
      (node (ref "R77") (pin "2") (pinfunction "2_2") (pintype "passive"))
    )
    (net (code "4") (name "Net-(C121-Pad1)") (class "Default")
      (node (ref "C121") (pin "1") (pinfunction "1_1") (pintype "passive"))
      (node (ref "C122") (pin "1") (pinfunction "1_1") (pintype "passive"))
      (node (ref "IC1") (pin "H32") (pinfunction "DIGPRVDD2_H32") (pintype "power_in"))
      (node (ref "R82") (pin "2") (pinfunction "2_2") (pintype "passive"))
    )
    (net (code "5") (name "Net-(C123-Pad1)") (class "Default")
      (node (ref "C123") (pin "1") (pinfunction "1_1") (pintype "passive"))
      (node (ref "C124") (pin "1") (pinfunction "1_1") (pintype "passive"))
      (node (ref "IC1") (pin "T32") (pinfunction "DIGPRVDD2_T32") (pintype "power_in"))
      (node (ref "R81") (pin "2") (pinfunction "2_2") (pintype "passive"))
    )
    (net (code "6") (name "Net-(C125-Pad1)") (class "Default")
      (node (ref "C125") (pin "1") (pinfunction "1_1") (pintype "passive"))
      (node (ref "C126") (pin "1") (pinfunction "1_1") (pintype "passive"))
      (node (ref "IC1") (pin "W33") (pinfunction "DIGPRVDD2_W33") (pintype "power_in"))
      (node (ref "R80") (pin "2") (pinfunction "2_2") (pintype "passive"))
    )
    (net (code "7") (name "Net-(C127-Pad1)") (class "Default")
      (node (ref "C127") (pin "1") (pinfunction "1_1") (pintype "passive"))
      (node (ref "C128") (pin "1") (pinfunction "1_1") (pintype "passive"))
      (node (ref "IC1") (pin "AH30") (pinfunction "DIGPRVDD2_AH30") (pintype "power_in"))
      (node (ref "R79") (pin "2") (pinfunction "2_2") (pintype "passive"))
    )
    (net (code "8") (name "Net-(C139-Pad1)") (class "Default")
      (node (ref "C139") (pin "1") (pinfunction "1_1") (pintype "passive"))
      (node (ref "FR33") (pin "2") (pinfunction "2_2") (pintype "passive"))
      (node (ref "R85") (pin "2") (pinfunction "2_2") (pintype "passive"))
    )
    (net (code "9") (name "Net-(C140-Pad1)") (class "Default")
      (node (ref "C140") (pin "1") (pinfunction "1_1") (pintype "passive"))
      (node (ref "FR32") (pin "1") (pinfunction "1_1") (pintype "passive"))
      (node (ref "R84") (pin "1") (pinfunction "1_1") (pintype "passive"))
    )
    (net (code "10") (name "Net-(IC1E-DIGPRPOC)") (class "Default")
      (node (ref "C119") (pin "1") (pinfunction "1_1") (pintype "passive"))
      (node (ref "C120") (pin "1") (pinfunction "1_1") (pintype "passive"))
      (node (ref "IC1") (pin "W31") (pinfunction "DIGPRPOC_W31") (pintype "power_in"))
      (node (ref "R83") (pin "2") (pinfunction "2_2") (pintype "passive"))
    )
    (net (code "11") (name "Net-(IC1E-VDD18_BIAS)") (class "Default")
      (node (ref "C132") (pin "1") (pinfunction "1_1") (pintype "passive"))
      (node (ref "FR29") (pin "1") (pinfunction "1_1") (pintype "passive"))
      (node (ref "IC1") (pin "E17") (pinfunction "VDD18_BIAS_E17") (pintype "power_in"))
    )
    (net (code "12") (name "Net-(IC1E-VDD18_DIG)") (class "Default")
      (node (ref "C117") (pin "1") (pinfunction "1_1") (pintype "passive"))
      (node (ref "IC1") (pin "D24") (pinfunction "VDD18_DIG_D24") (pintype "power_in"))
      (node (ref "R78") (pin "1") (pinfunction "1_1") (pintype "passive"))
    )
    (net (code "13") (name "Net-(IC1E-VDD18_LDO_RX)") (class "Default")
      (node (ref "C135") (pin "1") (pinfunction "1_1") (pintype "passive"))
      (node (ref "FR26") (pin "2") (pinfunction "2_2") (pintype "passive"))
      (node (ref "IC1") (pin "AE3") (pinfunction "VDD18_TIA_RFE_AE3") (pintype "power_in"))
      (node (ref "IC1") (pin "AF4") (pinfunction "VDD18_LDO_RX_AF4") (pintype "power_in"))
    )
    (net (code "14") (name "Net-(IC1E-VDD18_LDO_TX)") (class "Default")
      (node (ref "C136") (pin "1") (pinfunction "1_1") (pintype "passive"))
      (node (ref "FR25") (pin "2") (pinfunction "2_2") (pintype "passive"))
      (node (ref "IC1") (pin "N1") (pinfunction "VDD18_LDO_TX_N1") (pintype "power_in"))
    )
    (net (code "15") (name "Net-(IC1E-VDD18_RXBUF)") (class "Default")
      (node (ref "C137") (pin "1") (pinfunction "1_1") (pintype "passive"))
      (node (ref "FR33") (pin "1") (pinfunction "1_1") (pintype "passive"))
      (node (ref "IC1") (pin "AM26") (pinfunction "VDD18_RXBUF_AM26") (pintype "power_in"))
    )
    (net (code "16") (name "Net-(IC1E-VDD18_SXR)") (class "Default")
      (node (ref "C134") (pin "1") (pinfunction "1_1") (pintype "passive"))
      (node (ref "FR27") (pin "1") (pinfunction "1_1") (pintype "passive"))
      (node (ref "IC1") (pin "AM18") (pinfunction "VDD18_SXR_AM18") (pintype "power_in"))
    )
    (net (code "17") (name "Net-(IC1E-VDD18_TRF)") (class "Default")
      (node (ref "C131") (pin "1") (pinfunction "1_1") (pintype "passive"))
      (node (ref "FR30") (pin "1") (pinfunction "1_1") (pintype "passive"))
      (node (ref "IC1") (pin "D16") (pinfunction "VDD18_TRF_D16") (pintype "power_in"))
    )
    (net (code "18") (name "Net-(IC1E-VDD18_TXBUF)") (class "Default")
      (node (ref "C138") (pin "1") (pinfunction "1_1") (pintype "passive"))
      (node (ref "FR32") (pin "2") (pinfunction "2_2") (pintype "passive"))
      (node (ref "IC1") (pin "H6") (pinfunction "VDD18_TXBUF_H6") (pintype "power_in"))
    )
    (net (code "19") (name "Net-(IC1E-VDD18_VCO_CGEN)") (class "Default")
      (node (ref "C130") (pin "1") (pinfunction "1_1") (pintype "passive"))
      (node (ref "FR31") (pin "1") (pinfunction "1_1") (pintype "passive"))
      (node (ref "IC1") (pin "E21") (pinfunction "VDD18_VCO_CGEN_E21") (pintype "power_in"))
    )
    (net (code "20") (name "Net-(IC1E-VDD18_VCO_SXR)") (class "Default")
      (node (ref "C133") (pin "1") (pinfunction "1_1") (pintype "passive"))
      (node (ref "FR28") (pin "1") (pinfunction "1_1") (pintype "passive"))
      (node (ref "IC1") (pin "AK22") (pinfunction "VDD18_VCO_SXR_AK22") (pintype "power_in"))
    )
    (net (code "21") (name "Net-(IC1E-VDD18_VCO_SXT)") (class "Default")
      (node (ref "C129") (pin "1") (pinfunction "1_1") (pintype "passive"))
      (node (ref "FR24") (pin "1") (pinfunction "1_1") (pintype "passive"))
      (node (ref "IC1") (pin "G3") (pinfunction "VDD18_VCO_SXT_G3") (pintype "power_in"))
    )
    (net (code "22") (name "Net-(IC1F-DVDD_CGEN)") (class "Default")
      (node (ref "C84") (pin "1") (pinfunction "1_1") (pintype "passive"))
      (node (ref "C85") (pin "1") (pinfunction "1_1") (pintype "passive"))
      (node (ref "C86") (pin "1") (pinfunction "1_1") (pintype "passive"))
      (node (ref "FR3") (pin "1") (pinfunction "1_1") (pintype "passive"))
      (node (ref "IC1") (pin "A17") (pinfunction "DVDD_CGEN_A17") (pintype "power_in"))
      (node (ref "IC1") (pin "C25") (pinfunction "VDD12_DIG_C25") (pintype "power_in"))
      (node (ref "IC1") (pin "F24") (pinfunction "VDD_SPI_BUF_F24") (pintype "power_in"))
    )
    (net (code "23") (name "Net-(IC1F-DVDD_SXR)") (class "Default")
      (node (ref "C88") (pin "1") (pinfunction "1_1") (pintype "passive"))
      (node (ref "FR1") (pin "1") (pinfunction "1_1") (pintype "passive"))
      (node (ref "IC1") (pin "AL21") (pinfunction "DVDD_SXR_AL21") (pintype "power_in"))
    )
    (net (code "24") (name "Net-(IC1F-DVDD_SXT)") (class "Default")
      (node (ref "C87") (pin "2") (pinfunction "2_2") (pintype "passive"))
      (node (ref "FR2") (pin "1") (pinfunction "1_1") (pintype "passive"))
      (node (ref "IC1") (pin "M4") (pinfunction "DVDD_SXT_M4") (pintype "power_in"))
    )
    (net (code "25") (name "Net-(IC1F-VDD12O_VCO_SXT)") (class "Default")
      (node (ref "C109") (pin "2") (pinfunction "2_2") (pintype "passive"))
      (node (ref "FR4") (pin "1") (pinfunction "1_1") (pintype "passive"))
      (node (ref "IC1") (pin "J5") (pinfunction "VDD12O_VCO_SXT_J5") (pintype "power_in"))
      (node (ref "IC1") (pin "K6") (pinfunction "VDD12_VCO_SXT_K6") (pintype "power_in"))
    )
    (net (code "26") (name "Net-(IC1F-VDD12_LNA_RFE)") (class "Default")
      (node (ref "C106") (pin "1") (pinfunction "1_1") (pintype "passive"))
      (node (ref "FR8") (pin "1") (pinfunction "1_1") (pintype "passive"))
      (node (ref "IC1") (pin "AG5") (pinfunction "VDD12_LNA_RFE_AG5") (pintype "power_in"))
    )
    (net (code "27") (name "Net-(IC1F-VDD12_RXBUF)") (class "Default")
      (node (ref "C102") (pin "1") (pinfunction "1_1") (pintype "passive"))
      (node (ref "IC1") (pin "AP26") (pinfunction "VDD12_RXBUF_AP26") (pintype "power_in"))
      (node (ref "R77") (pin "1") (pinfunction "1_1") (pintype "passive"))
    )
    (net (code "28") (name "Net-(IC1F-VDD12_TIA_RFE)") (class "Default")
      (node (ref "C107") (pin "2") (pinfunction "2_2") (pintype "passive"))
      (node (ref "FR7") (pin "1") (pinfunction "1_1") (pintype "passive"))
      (node (ref "IC1") (pin "AD6") (pinfunction "VDD12_TIA_RFE_AD6") (pintype "power_in"))
    )
    (net (code "29") (name "Net-(IC1F-VDD12_TXBUF)") (class "Default")
      (node (ref "C95") (pin "1") (pinfunction "1_1") (pintype "passive"))
      (node (ref "IC1") (pin "G5") (pinfunction "VDD12_TXBUF_G5") (pintype "power_in"))
      (node (ref "R76") (pin "1") (pinfunction "1_1") (pintype "passive"))
    )
    (net (code "30") (name "Net-(IC1F-VDD12_VCO_SXR)") (class "Default")
      (node (ref "C103") (pin "1") (pinfunction "1_1") (pintype "passive"))
      (node (ref "FR11") (pin "1") (pinfunction "1_1") (pintype "passive"))
      (node (ref "IC1") (pin "AN23") (pinfunction "VDD12_VCO_SXR_AN23") (pintype "power_in"))
    )
    (net (code "31") (name "Net-(IC1F-VDD14_LNA_RFE)") (class "Default")
      (node (ref "C113") (pin "1") (pinfunction "1_1") (pintype "passive"))
      (node (ref "FR22") (pin "1") (pinfunction "1_1") (pintype "passive"))
      (node (ref "IC1") (pin "AF6") (pinfunction "VDD14_LNA_RFE_AF6") (pintype "power_in"))
    )
    (net (code "32") (name "Net-(IC1F-VDD14_RBB)") (class "Default")
      (node (ref "C115") (pin "1") (pinfunction "1_1") (pintype "passive"))
      (node (ref "FR20") (pin "1") (pinfunction "1_1") (pintype "passive"))
      (node (ref "IC1") (pin "AD4") (pinfunction "VDD14_RBB_AD4") (pintype "power_in"))
    )
    (net (code "33") (name "Net-(IC1F-VDD14_TIA_RFE)") (class "Default")
      (node (ref "C114") (pin "1") (pinfunction "1_1") (pintype "passive"))
      (node (ref "FR21") (pin "1") (pinfunction "1_1") (pintype "passive"))
      (node (ref "IC1") (pin "AF2") (pinfunction "VDD14_TIA_RFE_AF2") (pintype "power_in"))
    )
    (net (code "34") (name "Net-(IC1F-VDD14_VCO_CGEN)") (class "Default")
      (node (ref "C112") (pin "1") (pinfunction "1_1") (pintype "passive"))
      (node (ref "FR23") (pin "1") (pinfunction "1_1") (pintype "passive"))
      (node (ref "IC1") (pin "C21") (pinfunction "VDD14_VCO_CGEN_C21") (pintype "power_in"))
    )
    (net (code "35") (name "Net-(IC1F-VDDO_DIV_SXT)") (class "Default")
      (node (ref "C111") (pin "1") (pinfunction "1_1") (pintype "passive"))
      (node (ref "FR18") (pin "1") (pinfunction "1_1") (pintype "passive"))
      (node (ref "IC1") (pin "K2") (pinfunction "VDDO_DIV_SXT_K2") (pintype "power_in"))
      (node (ref "IC1") (pin "L5") (pinfunction "VDD_DIV_SXT_L5") (pintype "power_in"))
    )
    (net (code "36") (name "Net-(IC1F-VDDO_TLOBUF_TRF)") (class "Default")
      (node (ref "C97") (pin "1") (pinfunction "1_1") (pintype "passive"))
      (node (ref "FR17") (pin "1") (pinfunction "1_1") (pintype "passive"))
      (node (ref "IC1") (pin "D6") (pinfunction "VDDO_TLOBUF_TRF_D6") (pintype "power_in"))
      (node (ref "IC1") (pin "F8") (pinfunction "VDD_TLOBUF_TRF_F8") (pintype "power_in"))
    )
    (net (code "37") (name "Net-(IC1F-VDD_AFE)") (class "Default")
      (node (ref "C101") (pin "1") (pinfunction "1_1") (pintype "passive"))
      (node (ref "FR13") (pin "1") (pinfunction "1_1") (pintype "passive"))
      (node (ref "IC1") (pin "AJ25") (pinfunction "VDD_AFE_AJ25") (pintype "power_in"))
    )
    (net (code "38") (name "Net-(IC1F-VDD_CP_CGEN)") (class "Default")
      (node (ref "C100") (pin "2") (pinfunction "2_2") (pintype "passive"))
      (node (ref "FR14") (pin "1") (pinfunction "1_1") (pintype "passive"))
      (node (ref "IC1") (pin "F20") (pinfunction "VDD_CP_CGEN_F20") (pintype "power_in"))
    )
    (net (code "39") (name "Net-(IC1F-VDD_CP_SXR)") (class "Default")
      (node (ref "C105") (pin "1") (pinfunction "1_1") (pintype "passive"))
      (node (ref "FR9") (pin "1") (pinfunction "1_1") (pintype "passive"))
      (node (ref "IC1") (pin "AL19") (pinfunction "VDD_CP_SXR_AL19") (pintype "power_in"))
    )
    (net (code "40") (name "Net-(IC1F-VDD_CP_SXT)") (class "Default")
      (node (ref "C108") (pin "1") (pinfunction "1_1") (pintype "passive"))
      (node (ref "FR5") (pin "1") (pinfunction "1_1") (pintype "passive"))
      (node (ref "IC1") (pin "J3") (pinfunction "VDD_CP_SXT_J3") (pintype "power_in"))
    )
    (net (code "41") (name "Net-(IC1F-VDD_DIV_CGEN)") (class "Default")
      (node (ref "C99") (pin "1") (pinfunction "1_1") (pintype "passive"))
      (node (ref "FR15") (pin "1") (pinfunction "1_1") (pintype "passive"))
      (node (ref "IC1") (pin "E19") (pinfunction "VDD_DIV_CGEN_E19") (pintype "power_in"))
    )
    (net (code "42") (name "Net-(IC1F-VDD_DIV_SXR)") (class "Default")
      (node (ref "C104") (pin "1") (pinfunction "1_1") (pintype "passive"))
      (node (ref "FR10") (pin "1") (pinfunction "1_1") (pintype "passive"))
      (node (ref "IC1") (pin "AM20") (pinfunction "VDD_DIV_SXR_AM20") (pintype "power_in"))
    )
    (net (code "43") (name "Net-(IC1F-VDD_MXLOBUF_RFE)") (class "Default")
      (node (ref "C116") (pin "1") (pinfunction "1_1") (pintype "passive"))
      (node (ref "FR19") (pin "1") (pinfunction "1_1") (pintype "passive"))
      (node (ref "IC1") (pin "AN17") (pinfunction "VDD_MXLOBUF_RFE_AN17") (pintype "power_in"))
    )
    (net (code "44") (name "Net-(IC1F-VDD_TBB)") (class "Default")
      (node (ref "C96") (pin "1") (pinfunction "1_1") (pintype "passive"))
      (node (ref "FR6") (pin "1") (pinfunction "1_1") (pintype "passive"))
      (node (ref "IC1") (pin "P4") (pinfunction "VDD_TBB_P4") (pintype "power_in"))
    )
    (net (code "45") (name "Net-(IC1F-VDD_TPAD_TRF)") (class "Default")
      (node (ref "C98") (pin "1") (pinfunction "1_1") (pintype "passive"))
      (node (ref "FR16") (pin "1") (pinfunction "1_1") (pintype "passive"))
      (node (ref "IC1") (pin "B16") (pinfunction "VDD_TPAD_TRF_B16") (pintype "power_in"))
    )
    (net (code "46") (name "VCC1P4_LMS1") (class "Default")
      (node (ref "FR18") (pin "2") (pinfunction "2_2") (pintype "passive"))
      (node (ref "FR19") (pin "2") (pinfunction "2_2") (pintype "passive"))
      (node (ref "FR20") (pin "2") (pinfunction "2_2") (pintype "passive"))
      (node (ref "FR21") (pin "2") (pinfunction "2_2") (pintype "passive"))
      (node (ref "FR22") (pin "2") (pinfunction "2_2") (pintype "passive"))
      (node (ref "FR23") (pin "2") (pinfunction "2_2") (pintype "passive"))
      (node (ref "R74") (pin "1") (pinfunction "1_1") (pintype "passive"))
    )
    (net (code "47") (name "VCC1P8_LMS1") (class "Default")
      (node (ref "FR24") (pin "2") (pinfunction "2_2") (pintype "passive"))
      (node (ref "FR25") (pin "1") (pinfunction "1_1") (pintype "passive"))
      (node (ref "FR26") (pin "1") (pinfunction "1_1") (pintype "passive"))
      (node (ref "FR27") (pin "2") (pinfunction "2_2") (pintype "passive"))
      (node (ref "FR28") (pin "2") (pinfunction "2_2") (pintype "passive"))
      (node (ref "FR29") (pin "2") (pinfunction "2_2") (pintype "passive"))
      (node (ref "FR30") (pin "2") (pinfunction "2_2") (pintype "passive"))
      (node (ref "FR31") (pin "2") (pinfunction "2_2") (pintype "passive"))
      (node (ref "R78") (pin "2") (pinfunction "2_2") (pintype "passive"))
      (node (ref "R84") (pin "2") (pinfunction "2_2") (pintype "passive"))
      (node (ref "R85") (pin "1") (pinfunction "1_1") (pintype "passive"))
    )
    (net (code "48") (name "VCC1P25_LMS1") (class "Default")
      (node (ref "FR1") (pin "2") (pinfunction "2_2") (pintype "passive"))
      (node (ref "FR10") (pin "2") (pinfunction "2_2") (pintype "passive"))
      (node (ref "FR11") (pin "2") (pinfunction "2_2") (pintype "passive"))
      (node (ref "FR12") (pin "2") (pinfunction "2_2") (pintype "passive"))
      (node (ref "FR13") (pin "2") (pinfunction "2_2") (pintype "passive"))
      (node (ref "FR14") (pin "2") (pinfunction "2_2") (pintype "passive"))
      (node (ref "FR15") (pin "2") (pinfunction "2_2") (pintype "passive"))
      (node (ref "FR16") (pin "2") (pinfunction "2_2") (pintype "passive"))
      (node (ref "FR17") (pin "2") (pinfunction "2_2") (pintype "passive"))
      (node (ref "FR2") (pin "2") (pinfunction "2_2") (pintype "passive"))
      (node (ref "FR3") (pin "2") (pinfunction "2_2") (pintype "passive"))
      (node (ref "FR4") (pin "2") (pinfunction "2_2") (pintype "passive"))
      (node (ref "FR5") (pin "2") (pinfunction "2_2") (pintype "passive"))
      (node (ref "FR6") (pin "2") (pinfunction "2_2") (pintype "passive"))
      (node (ref "FR7") (pin "2") (pinfunction "2_2") (pintype "passive"))
      (node (ref "FR8") (pin "2") (pinfunction "2_2") (pintype "passive"))
      (node (ref "FR9") (pin "2") (pinfunction "2_2") (pintype "passive"))
      (node (ref "R75") (pin "1") (pinfunction "1_1") (pintype "passive"))
    )
    (net (code "49") (name "VDIO_LMS") (class "Default")
      (node (ref "C118") (pin "2") (pinfunction "2_2") (pintype "passive"))
      (node (ref "R79") (pin "1") (pinfunction "1_1") (pintype "passive"))
      (node (ref "R80") (pin "1") (pinfunction "1_1") (pintype "passive"))
      (node (ref "R81") (pin "1") (pinfunction "1_1") (pintype "passive"))
      (node (ref "R82") (pin "1") (pinfunction "1_1") (pintype "passive"))
      (node (ref "R83") (pin "1") (pinfunction "1_1") (pintype "passive"))
    )
  )
)
